# Dual_VCLFO_MAIN.net
KiCad netlist of a schematic drawn in EAGLE
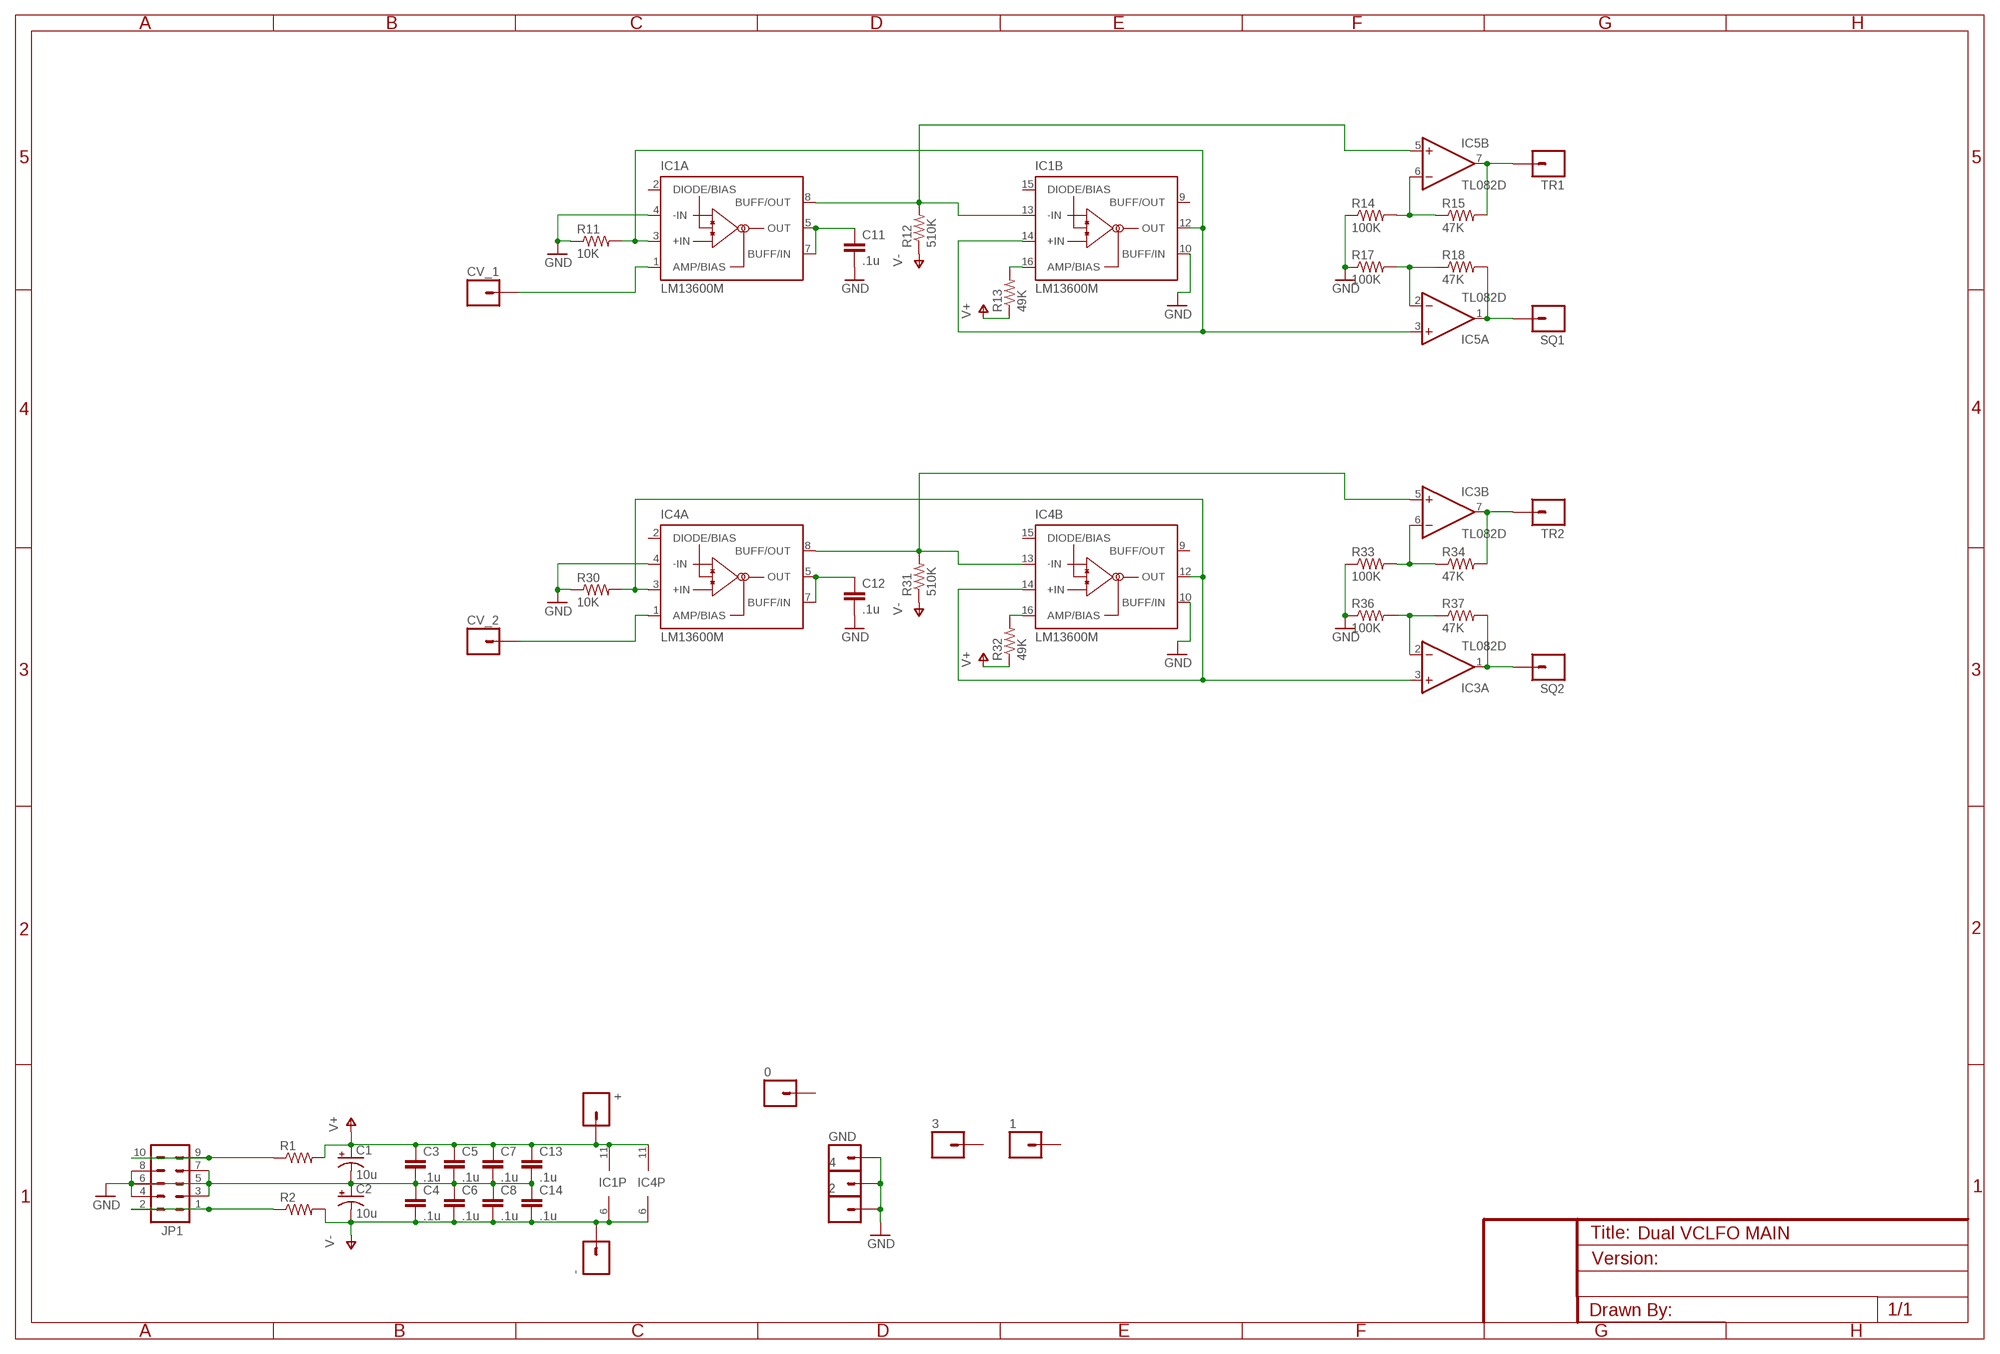
[diagram p0: schematic, sheet 1]

(export (version "E")
  (design (tool "Eeschema 10.0.6"))
  (components
    (comp (ref "+")
      (value "M01PTH")
      (footprint "eagle-import:1X01")
      (libsource (lib "eagle-import") (part "M01PTH"))
    )
    (comp (ref "-")
      (value "M01PTH")
      (footprint "eagle-import:1X01")
      (libsource (lib "eagle-import") (part "M01PTH"))
    )
    (comp (ref "0")
      (value "M01PTH")
      (footprint "eagle-import:1X01")
      (libsource (lib "eagle-import") (part "M01PTH"))
    )
    (comp (ref "1")
      (value "M01PTH")
      (footprint "eagle-import:1X01")
      (libsource (lib "eagle-import") (part "M01PTH"))
    )
    (comp (ref "2")
      (value "M01PTH")
      (footprint "eagle-import:1X01")
      (libsource (lib "eagle-import") (part "M01PTH"))
    )
    (comp (ref "3")
      (value "M01PTH")
      (footprint "eagle-import:1X01")
      (libsource (lib "eagle-import") (part "M01PTH"))
    )
    (comp (ref "4")
      (value "M01PTH")
      (footprint "eagle-import:1X01")
      (libsource (lib "eagle-import") (part "M01PTH"))
    )
    (comp (ref "C1")
      (value "10u")
      (footprint "eagle-import:CPOL-RADIAL-10UF-25V")
      (libsource (lib "eagle-import") (part "CAP_POLPTH2"))
    )
    (comp (ref "C2")
      (value "10u")
      (footprint "eagle-import:CPOL-RADIAL-10UF-25V")
      (libsource (lib "eagle-import") (part "CAP_POLPTH2"))
    )
    (comp (ref "C3")
      (value ".1u")
      (footprint "eagle-import:0805")
      (libsource (lib "eagle-import") (part "CAP0805"))
    )
    (comp (ref "C4")
      (value ".1u")
      (footprint "eagle-import:0805")
      (libsource (lib "eagle-import") (part "CAP0805"))
    )
    (comp (ref "C5")
      (value ".1u")
      (footprint "eagle-import:0805")
      (libsource (lib "eagle-import") (part "CAP0805"))
    )
    (comp (ref "C6")
      (value ".1u")
      (footprint "eagle-import:0805")
      (libsource (lib "eagle-import") (part "CAP0805"))
    )
    (comp (ref "C7")
      (value ".1u")
      (footprint "eagle-import:0805")
      (libsource (lib "eagle-import") (part "CAP0805"))
    )
    (comp (ref "C8")
      (value ".1u")
      (footprint "eagle-import:0805")
      (libsource (lib "eagle-import") (part "CAP0805"))
    )
    (comp (ref "C11")
      (value ".1u")
      (footprint "eagle-import:CAP-PTH-5MM")
      (libsource (lib "eagle-import") (part "CAPPTH1"))
    )
    (comp (ref "C12")
      (value ".1u")
      (footprint "eagle-import:CAP-PTH-5MM")
      (libsource (lib "eagle-import") (part "CAPPTH1"))
    )
    (comp (ref "C13")
      (value ".1u")
      (footprint "eagle-import:0805")
      (libsource (lib "eagle-import") (part "CAP0805"))
    )
    (comp (ref "C14")
      (value ".1u")
      (footprint "eagle-import:0805")
      (libsource (lib "eagle-import") (part "CAP0805"))
    )
    (comp (ref "CV_1")
      (value "M01PTH")
      (footprint "eagle-import:1X01")
      (libsource (lib "eagle-import") (part "M01PTH"))
    )
    (comp (ref "CV_2")
      (value "M01PTH")
      (footprint "eagle-import:1X01")
      (libsource (lib "eagle-import") (part "M01PTH"))
    )
    (comp (ref "GND")
      (value "M01PTH")
      (footprint "eagle-import:1X01")
      (libsource (lib "eagle-import") (part "M01PTH"))
    )
    (comp (ref "IC1")
      (value "LM13600M")
      (footprint "eagle-import:SO16")
      (libsource (lib "eagle-import") (part "LM13600M"))
    )
    (comp (ref "IC3")
      (value "TL082D")
      (footprint "eagle-import:SO08")
      (libsource (lib "eagle-import") (part "TL082D"))
    )
    (comp (ref "IC4")
      (value "LM13600M")
      (footprint "eagle-import:SO16")
      (libsource (lib "eagle-import") (part "LM13600M"))
    )
    (comp (ref "IC5")
      (value "TL082D")
      (footprint "eagle-import:SO08")
      (libsource (lib "eagle-import") (part "TL082D"))
    )
    (comp (ref "JP1")
      (value "M05X2PTH")
      (footprint "eagle-import:AVR_ICSP")
      (libsource (lib "eagle-import") (part "M05X2PTH"))
    )
    (comp (ref "R1")
      (value "RESISTOR0805-RES")
      (footprint "eagle-import:0805")
      (libsource (lib "eagle-import") (part "RESISTOR0805-RES"))
    )
    (comp (ref "R2")
      (value "RESISTOR0805-RES")
      (footprint "eagle-import:0805")
      (libsource (lib "eagle-import") (part "RESISTOR0805-RES"))
    )
    (comp (ref "R11")
      (value "10K")
      (footprint "eagle-import:0805")
      (libsource (lib "eagle-import") (part "RESISTOR0805-RES"))
    )
    (comp (ref "R12")
      (value "510K")
      (footprint "eagle-import:0805")
      (libsource (lib "eagle-import") (part "RESISTOR0805-RES"))
    )
    (comp (ref "R13")
      (value "49K")
      (footprint "eagle-import:0805")
      (libsource (lib "eagle-import") (part "RESISTOR0805-RES"))
    )
    (comp (ref "R14")
      (value "100K")
      (footprint "eagle-import:0805")
      (libsource (lib "eagle-import") (part "RESISTOR0805-RES"))
    )
    (comp (ref "R15")
      (value "47K")
      (footprint "eagle-import:0805")
      (libsource (lib "eagle-import") (part "RESISTOR0805-RES"))
    )
    (comp (ref "R17")
      (value "100K")
      (footprint "eagle-import:0805")
      (libsource (lib "eagle-import") (part "RESISTOR0805-RES"))
    )
    (comp (ref "R18")
      (value "47K")
      (footprint "eagle-import:0805")
      (libsource (lib "eagle-import") (part "RESISTOR0805-RES"))
    )
    (comp (ref "R30")
      (value "10K")
      (footprint "eagle-import:0805")
      (libsource (lib "eagle-import") (part "RESISTOR0805-RES"))
    )
    (comp (ref "R31")
      (value "510K")
      (footprint "eagle-import:0805")
      (libsource (lib "eagle-import") (part "RESISTOR0805-RES"))
    )
    (comp (ref "R32")
      (value "49K")
      (footprint "eagle-import:0805")
      (libsource (lib "eagle-import") (part "RESISTOR0805-RES"))
    )
    (comp (ref "R33")
      (value "100K")
      (footprint "eagle-import:0805")
      (libsource (lib "eagle-import") (part "RESISTOR0805-RES"))
    )
    (comp (ref "R34")
      (value "47K")
      (footprint "eagle-import:0805")
      (libsource (lib "eagle-import") (part "RESISTOR0805-RES"))
    )
    (comp (ref "R36")
      (value "100K")
      (footprint "eagle-import:0805")
      (libsource (lib "eagle-import") (part "RESISTOR0805-RES"))
    )
    (comp (ref "R37")
      (value "47K")
      (footprint "eagle-import:0805")
      (libsource (lib "eagle-import") (part "RESISTOR0805-RES"))
    )
    (comp (ref "SQ1")
      (value "M01PTH")
      (footprint "eagle-import:1X01")
      (libsource (lib "eagle-import") (part "M01PTH"))
    )
    (comp (ref "SQ2")
      (value "M01PTH")
      (footprint "eagle-import:1X01")
      (libsource (lib "eagle-import") (part "M01PTH"))
    )
    (comp (ref "TR1")
      (value "M01PTH")
      (footprint "eagle-import:1X01")
      (libsource (lib "eagle-import") (part "M01PTH"))
    )
    (comp (ref "TR2")
      (value "M01PTH")
      (footprint "eagle-import:1X01")
      (libsource (lib "eagle-import") (part "M01PTH"))
    )
  )
  (nets
    (net (code "1") (name "GND") (class "Default")
      (node (ref "2") (pin "1") (pinfunction "1_1") (pintype "passive"))
      (node (ref "4") (pin "1") (pinfunction "1_1") (pintype "passive"))
      (node (ref "C1") (pin "2") (pinfunction "-_2") (pintype "passive"))
      (node (ref "C11") (pin "2") (pinfunction "2_2") (pintype "passive"))
      (node (ref "C12") (pin "2") (pinfunction "2_2") (pintype "passive"))
      (node (ref "C13") (pin "2") (pinfunction "2_2") (pintype "passive"))
      (node (ref "C14") (pin "1") (pinfunction "1_1") (pintype "passive"))
      (node (ref "C2") (pin "1") (pinfunction "+_1") (pintype "passive"))
      (node (ref "C3") (pin "2") (pinfunction "2_2") (pintype "passive"))
      (node (ref "C4") (pin "1") (pinfunction "1_1") (pintype "passive"))
      (node (ref "C5") (pin "2") (pinfunction "2_2") (pintype "passive"))
      (node (ref "C6") (pin "1") (pinfunction "1_1") (pintype "passive"))
      (node (ref "C7") (pin "2") (pinfunction "2_2") (pintype "passive"))
      (node (ref "C8") (pin "1") (pinfunction "1_1") (pintype "passive"))
      (node (ref "GND") (pin "1") (pinfunction "1_1") (pintype "passive"))
      (node (ref "IC1") (pin "10") (pinfunction "BUFF/IN_10") (pintype "input"))
      (node (ref "IC1") (pin "4") (pinfunction "-IN_4") (pintype "input"))
      (node (ref "IC4") (pin "10") (pinfunction "BUFF/IN_10") (pintype "input"))
      (node (ref "IC4") (pin "4") (pinfunction "-IN_4") (pintype "input"))
      (node (ref "JP1") (pin "3") (pinfunction "3_3") (pintype "passive"))
      (node (ref "JP1") (pin "4") (pinfunction "4_4") (pintype "passive"))
      (node (ref "JP1") (pin "5") (pinfunction "5_5") (pintype "passive"))
      (node (ref "JP1") (pin "6") (pinfunction "6_6") (pintype "passive"))
      (node (ref "JP1") (pin "7") (pinfunction "7_7") (pintype "passive"))
      (node (ref "JP1") (pin "8") (pinfunction "8_8") (pintype "passive"))
      (node (ref "R11") (pin "1") (pinfunction "1_1") (pintype "passive"))
      (node (ref "R14") (pin "1") (pinfunction "1_1") (pintype "passive"))
      (node (ref "R17") (pin "1") (pinfunction "1_1") (pintype "passive"))
      (node (ref "R30") (pin "1") (pinfunction "1_1") (pintype "passive"))
      (node (ref "R33") (pin "1") (pinfunction "1_1") (pintype "passive"))
      (node (ref "R36") (pin "1") (pinfunction "1_1") (pintype "passive"))
    )
    (net (code "2") (name "Net-(IC1A-+IN)") (class "Default")
      (node (ref "IC1") (pin "12") (pinfunction "OUT_12") (pintype "output"))
      (node (ref "IC1") (pin "14") (pinfunction "+IN_14") (pintype "input"))
      (node (ref "IC1") (pin "3") (pinfunction "+IN_3") (pintype "input"))
      (node (ref "IC5") (pin "3") (pinfunction "+IN_3") (pintype "input"))
      (node (ref "R11") (pin "2") (pinfunction "2_2") (pintype "passive"))
    )
    (net (code "3") (name "Net-(IC1A-AMP{slash}BIAS)") (class "Default")
      (node (ref "CV_1") (pin "1") (pinfunction "1_1") (pintype "passive"))
      (node (ref "IC1") (pin "1") (pinfunction "AMP/BIAS_1") (pintype "passive"))
    )
    (net (code "4") (name "Net-(IC1A-BUFF{slash}IN)") (class "Default")
      (node (ref "C11") (pin "1") (pinfunction "1_1") (pintype "passive"))
      (node (ref "IC1") (pin "5") (pinfunction "OUT_5") (pintype "output"))
      (node (ref "IC1") (pin "7") (pinfunction "BUFF/IN_7") (pintype "input"))
    )
    (net (code "5") (name "Net-(IC1A-BUFF{slash}OUT)") (class "Default")
      (node (ref "IC1") (pin "13") (pinfunction "-IN_13") (pintype "input"))
      (node (ref "IC1") (pin "8") (pinfunction "BUFF/OUT_8") (pintype "output"))
      (node (ref "IC5") (pin "5") (pinfunction "+IN_5") (pintype "input"))
      (node (ref "R12") (pin "2") (pinfunction "2_2") (pintype "passive"))
    )
    (net (code "6") (name "Net-(IC1B-AMP{slash}BIAS)") (class "Default")
      (node (ref "IC1") (pin "16") (pinfunction "AMP/BIAS_16") (pintype "passive"))
      (node (ref "R13") (pin "2") (pinfunction "2_2") (pintype "passive"))
    )
    (net (code "7") (name "Net-(IC3A-+IN)") (class "Default")
      (node (ref "IC3") (pin "3") (pinfunction "+IN_3") (pintype "input"))
      (node (ref "IC4") (pin "12") (pinfunction "OUT_12") (pintype "output"))
      (node (ref "IC4") (pin "14") (pinfunction "+IN_14") (pintype "input"))
      (node (ref "IC4") (pin "3") (pinfunction "+IN_3") (pintype "input"))
      (node (ref "R30") (pin "2") (pinfunction "2_2") (pintype "passive"))
    )
    (net (code "8") (name "Net-(IC3A--IN)") (class "Default")
      (node (ref "IC3") (pin "2") (pinfunction "-IN_2") (pintype "input"))
      (node (ref "R36") (pin "2") (pinfunction "2_2") (pintype "passive"))
      (node (ref "R37") (pin "1") (pinfunction "1_1") (pintype "passive"))
    )
    (net (code "9") (name "Net-(IC3A-OUT)") (class "Default")
      (node (ref "IC3") (pin "1") (pinfunction "OUT_1") (pintype "output"))
      (node (ref "R37") (pin "2") (pinfunction "2_2") (pintype "passive"))
      (node (ref "SQ2") (pin "1") (pinfunction "1_1") (pintype "passive"))
    )
    (net (code "10") (name "Net-(IC3B-+IN)") (class "Default")
      (node (ref "IC3") (pin "5") (pinfunction "+IN_5") (pintype "input"))
      (node (ref "IC4") (pin "13") (pinfunction "-IN_13") (pintype "input"))
      (node (ref "IC4") (pin "8") (pinfunction "BUFF/OUT_8") (pintype "output"))
      (node (ref "R31") (pin "2") (pinfunction "2_2") (pintype "passive"))
    )
    (net (code "11") (name "Net-(IC3B--IN)") (class "Default")
      (node (ref "IC3") (pin "6") (pinfunction "-IN_6") (pintype "input"))
      (node (ref "R33") (pin "2") (pinfunction "2_2") (pintype "passive"))
      (node (ref "R34") (pin "1") (pinfunction "1_1") (pintype "passive"))
    )
    (net (code "12") (name "Net-(IC3B-OUT)") (class "Default")
      (node (ref "IC3") (pin "7") (pinfunction "OUT_7") (pintype "output"))
      (node (ref "R34") (pin "2") (pinfunction "2_2") (pintype "passive"))
      (node (ref "TR2") (pin "1") (pinfunction "1_1") (pintype "passive"))
    )
    (net (code "13") (name "Net-(IC4A-AMP{slash}BIAS)") (class "Default")
      (node (ref "CV_2") (pin "1") (pinfunction "1_1") (pintype "passive"))
      (node (ref "IC4") (pin "1") (pinfunction "AMP/BIAS_1") (pintype "passive"))
    )
    (net (code "14") (name "Net-(IC4A-BUFF{slash}IN)") (class "Default")
      (node (ref "C12") (pin "1") (pinfunction "1_1") (pintype "passive"))
      (node (ref "IC4") (pin "5") (pinfunction "OUT_5") (pintype "output"))
      (node (ref "IC4") (pin "7") (pinfunction "BUFF/IN_7") (pintype "input"))
    )
    (net (code "15") (name "Net-(IC4B-AMP{slash}BIAS)") (class "Default")
      (node (ref "IC4") (pin "16") (pinfunction "AMP/BIAS_16") (pintype "passive"))
      (node (ref "R32") (pin "2") (pinfunction "2_2") (pintype "passive"))
    )
    (net (code "16") (name "Net-(IC5A--IN)") (class "Default")
      (node (ref "IC5") (pin "2") (pinfunction "-IN_2") (pintype "input"))
      (node (ref "R17") (pin "2") (pinfunction "2_2") (pintype "passive"))
      (node (ref "R18") (pin "1") (pinfunction "1_1") (pintype "passive"))
    )
    (net (code "17") (name "Net-(IC5A-OUT)") (class "Default")
      (node (ref "IC5") (pin "1") (pinfunction "OUT_1") (pintype "output"))
      (node (ref "R18") (pin "2") (pinfunction "2_2") (pintype "passive"))
      (node (ref "SQ1") (pin "1") (pinfunction "1_1") (pintype "passive"))
    )
    (net (code "18") (name "Net-(IC5B--IN)") (class "Default")
      (node (ref "IC5") (pin "6") (pinfunction "-IN_6") (pintype "input"))
      (node (ref "R14") (pin "2") (pinfunction "2_2") (pintype "passive"))
      (node (ref "R15") (pin "1") (pinfunction "1_1") (pintype "passive"))
    )
    (net (code "19") (name "Net-(IC5B-OUT)") (class "Default")
      (node (ref "IC5") (pin "7") (pinfunction "OUT_7") (pintype "output"))
      (node (ref "R15") (pin "2") (pinfunction "2_2") (pintype "passive"))
      (node (ref "TR1") (pin "1") (pinfunction "1_1") (pintype "passive"))
    )
    (net (code "20") (name "Net-(JP1-Pad1)") (class "Default")
      (node (ref "JP1") (pin "1") (pinfunction "1_1") (pintype "passive"))
      (node (ref "JP1") (pin "2") (pinfunction "2_2") (pintype "passive"))
      (node (ref "R2") (pin "1") (pinfunction "1_1") (pintype "passive"))
    )
    (net (code "21") (name "Net-(JP1-Pad10)") (class "Default")
      (node (ref "JP1") (pin "10") (pinfunction "10_10") (pintype "passive"))
      (node (ref "JP1") (pin "9") (pinfunction "9_9") (pintype "passive"))
      (node (ref "R1") (pin "1") (pinfunction "1_1") (pintype "passive"))
    )
    (net (code "22") (name "V+") (class "Default")
      (node (ref "+") (pin "1") (pinfunction "1_1") (pintype "passive"))
      (node (ref "C1") (pin "1") (pinfunction "+_1") (pintype "passive"))
      (node (ref "C13") (pin "1") (pinfunction "1_1") (pintype "passive"))
      (node (ref "C3") (pin "1") (pinfunction "1_1") (pintype "passive"))
      (node (ref "C5") (pin "1") (pinfunction "1_1") (pintype "passive"))
      (node (ref "C7") (pin "1") (pinfunction "1_1") (pintype "passive"))
      (node (ref "IC1") (pin "11") (pinfunction "V+_11") (pintype "power_in"))
      (node (ref "IC4") (pin "11") (pinfunction "V+_11") (pintype "power_in"))
      (node (ref "R1") (pin "2") (pinfunction "2_2") (pintype "passive"))
      (node (ref "R13") (pin "1") (pinfunction "1_1") (pintype "passive"))
      (node (ref "R32") (pin "1") (pinfunction "1_1") (pintype "passive"))
    )
    (net (code "23") (name "V-") (class "Default")
      (node (ref "-") (pin "1") (pinfunction "1_1") (pintype "passive"))
      (node (ref "C14") (pin "2") (pinfunction "2_2") (pintype "passive"))
      (node (ref "C2") (pin "2") (pinfunction "-_2") (pintype "passive"))
      (node (ref "C4") (pin "2") (pinfunction "2_2") (pintype "passive"))
      (node (ref "C6") (pin "2") (pinfunction "2_2") (pintype "passive"))
      (node (ref "C8") (pin "2") (pinfunction "2_2") (pintype "passive"))
      (node (ref "IC1") (pin "6") (pinfunction "V-_6") (pintype "power_in"))
      (node (ref "IC4") (pin "6") (pinfunction "V-_6") (pintype "power_in"))
      (node (ref "R12") (pin "1") (pinfunction "1_1") (pintype "passive"))
      (node (ref "R2") (pin "2") (pinfunction "2_2") (pintype "passive"))
      (node (ref "R31") (pin "1") (pinfunction "1_1") (pintype "passive"))
    )
    (net (code "24") (name "unconnected-(0-Pad1)") (class "Default")
      (node (ref "0") (pin "1") (pinfunction "1_1") (pintype "passive"))
    )
    (net (code "25") (name "unconnected-(1-Pad1)") (class "Default")
      (node (ref "1") (pin "1") (pinfunction "1_1") (pintype "passive"))
    )
    (net (code "26") (name "unconnected-(3-Pad1)") (class "Default")
      (node (ref "3") (pin "1") (pinfunction "1_1") (pintype "passive"))
    )
    (net (code "27") (name "unconnected-(IC1A-DIODE{slash}BIAS-Pad2)") (class "Default")
      (node (ref "IC1") (pin "2") (pinfunction "DIODE/BIAS_2") (pintype "passive"))
    )
    (net (code "28") (name "unconnected-(IC1B-BUFF{slash}OUT-Pad9)") (class "Default")
      (node (ref "IC1") (pin "9") (pinfunction "BUFF/OUT_9") (pintype "output"))
    )
    (net (code "29") (name "unconnected-(IC1B-DIODE{slash}BIAS-Pad15)") (class "Default")
      (node (ref "IC1") (pin "15") (pinfunction "DIODE/BIAS_15") (pintype "passive"))
    )
    (net (code "30") (name "unconnected-(IC4A-DIODE{slash}BIAS-Pad2)") (class "Default")
      (node (ref "IC4") (pin "2") (pinfunction "DIODE/BIAS_2") (pintype "passive"))
    )
    (net (code "31") (name "unconnected-(IC4B-BUFF{slash}OUT-Pad9)") (class "Default")
      (node (ref "IC4") (pin "9") (pinfunction "BUFF/OUT_9") (pintype "output"))
    )
    (net (code "32") (name "unconnected-(IC4B-DIODE{slash}BIAS-Pad15)") (class "Default")
      (node (ref "IC4") (pin "15") (pinfunction "DIODE/BIAS_15") (pintype "passive"))
    )
  )
)
